# Logic_Engine_v0_1.net
KiCad netlist of a schematic drawn in EAGLE
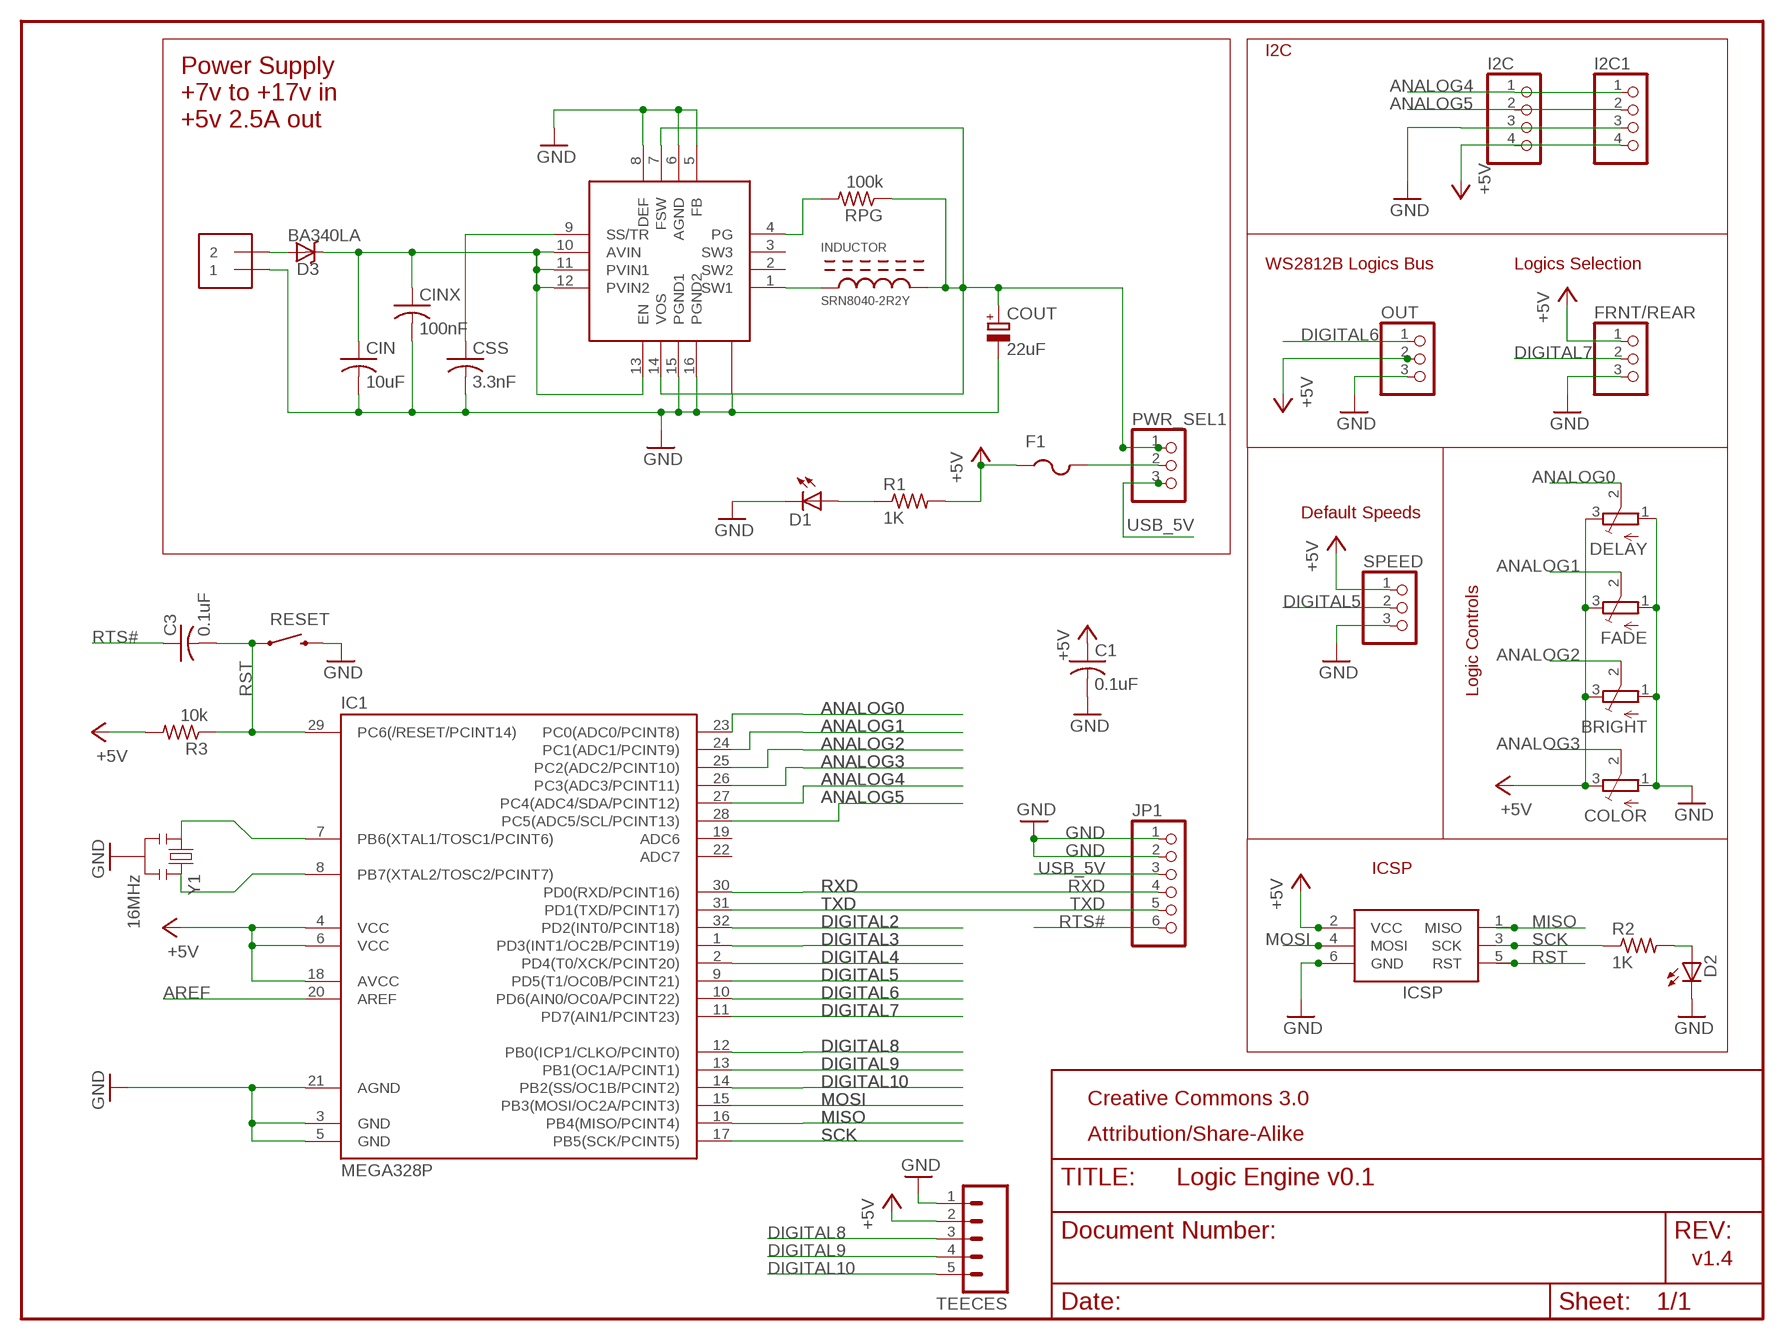
[diagram p0: schematic, sheet 1]

(export (version "E")
  (design (tool "Eeschema 10.0.6"))
  (components
    (comp (ref "BRIGHT")
      (value "TRIMPOT3364W")
      (footprint "eagle-import:3364")
      (libsource (lib "eagle-import") (part "TRIMPOT3364W"))
    )
    (comp (ref "C1")
      (value "0.1uF")
      (footprint "eagle-import:C0805K")
      (libsource (lib "eagle-import") (part "C-USC0805K"))
    )
    (comp (ref "C3")
      (value "0.1uF")
      (footprint "eagle-import:C0805K")
      (libsource (lib "eagle-import") (part "C-USC0805K"))
    )
    (comp (ref "CIN")
      (value "10uF")
      (footprint "eagle-import:C1206")
      (libsource (lib "eagle-import") (part "C-USC1206"))
    )
    (comp (ref "CINX")
      (value "100nF")
      (footprint "eagle-import:C0805K")
      (libsource (lib "eagle-import") (part "C-USC0805K"))
    )
    (comp (ref "COLOR")
      (value "TRIMPOT3364W")
      (footprint "eagle-import:3364")
      (libsource (lib "eagle-import") (part "TRIMPOT3364W"))
    )
    (comp (ref "COUT")
      (value "22uF")
      (footprint "eagle-import:CASE_B")
      (libsource (lib "eagle-import") (part "CAPACITOR_POL-CASE_B"))
    )
    (comp (ref "CSS")
      (value "3.3nF")
      (footprint "eagle-import:C0805K")
      (libsource (lib "eagle-import") (part "C-USC0805K"))
    )
    (comp (ref "D1")
      (value "LEDCHIPLED_1206")
      (footprint "eagle-import:CHIPLED_1206")
      (libsource (lib "eagle-import") (part "LEDCHIPLED_1206"))
    )
    (comp (ref "D2")
      (value "Green")
      (footprint "eagle-import:CHIPLED_1206")
      (libsource (lib "eagle-import") (part "LEDCHIPLED_1206"))
    )
    (comp (ref "D3")
      (value "BA340LA")
      (footprint "eagle-import:SMA-DIODE")
      (libsource (lib "eagle-import") (part "B340A"))
    )
    (comp (ref "DELAY")
      (value "TRIMPOT3364W")
      (footprint "eagle-import:3364")
      (libsource (lib "eagle-import") (part "TRIMPOT3364W"))
    )
    (comp (ref "EXT.PWR")
      (value "1X2-3.5MM")
      (footprint "eagle-import:1X2-3.5MM")
      (libsource (lib "eagle-import") (part "1X2-3.5MM"))
    )
    (comp (ref "F1")
      (value "PTCFUSE-1812")
      (footprint "eagle-import:1812")
      (libsource (lib "eagle-import") (part "PTCFUSE-1812"))
    )
    (comp (ref "FADE")
      (value "TRIMPOT3364W")
      (footprint "eagle-import:3364")
      (libsource (lib "eagle-import") (part "TRIMPOT3364W"))
    )
    (comp (ref "FRNT/REAR")
      (value "PINHD-1X3")
      (footprint "eagle-import:1X03")
      (libsource (lib "eagle-import") (part "PINHD-1X3"))
    )
    (comp (ref "I2C")
      (value "PINHD-1X4CB")
      (footprint "eagle-import:1X04-CB")
      (libsource (lib "eagle-import") (part "PINHD-1X4CB"))
    )
    (comp (ref "I2C1")
      (value "PINHD-1X4CB")
      (footprint "eagle-import:1X04-CB")
      (libsource (lib "eagle-import") (part "PINHD-1X4CB"))
    )
    (comp (ref "IC1")
      (value "MEGA328P")
      (footprint "eagle-import:TQFP32-08")
      (libsource (lib "eagle-import") (part "MEGA48/88/168-AU"))
    )
    (comp (ref "ICSP")
      (value "AVRISP-6")
      (footprint "eagle-import:AVRISP")
      (libsource (lib "eagle-import") (part "AVRISP-6"))
    )
    (comp (ref "INDUCTOR")
      (value "SRN8040-2R2Y")
      (footprint "eagle-import:SRN8040")
      (libsource (lib "eagle-import") (part "SRN8040"))
    )
    (comp (ref "JP1")
      (value "PINHD-1X6CLEAN")
      (footprint "eagle-import:1X06-CLEAN")
      (libsource (lib "eagle-import") (part "PINHD-1X6CLEAN"))
    )
    (comp (ref "OUT")
      (value "PINHD-1X3")
      (footprint "eagle-import:1X03")
      (libsource (lib "eagle-import") (part "PINHD-1X3"))
    )
    (comp (ref "PWR_SEL1")
      (value "PINHD-1X3")
      (footprint "eagle-import:1X03")
      (libsource (lib "eagle-import") (part "PINHD-1X3"))
    )
    (comp (ref "R1")
      (value "1K")
      (footprint "eagle-import:R0805")
      (libsource (lib "eagle-import") (part "R-US_R0805"))
    )
    (comp (ref "R2")
      (value "1K")
      (footprint "eagle-import:R0805")
      (libsource (lib "eagle-import") (part "R-US_R0805"))
    )
    (comp (ref "R3")
      (value "10k")
      (footprint "eagle-import:R0805")
      (libsource (lib "eagle-import") (part "R-US_R0805"))
    )
    (comp (ref "REG")
      (value "TPS62133")
      (footprint "eagle-import:TPS6213X")
      (libsource (lib "eagle-import") (part "TPS6213X"))
    )
    (comp (ref "RESET")
      (value "SWITCH-MOMENTARY-2SMD")
      (footprint "eagle-import:TACTILE_SWITCH_SMD")
      (libsource (lib "eagle-import") (part "SWITCH-MOMENTARY-2SMD"))
    )
    (comp (ref "RPG")
      (value "100k")
      (footprint "eagle-import:R0805")
      (libsource (lib "eagle-import") (part "R-US_R0805"))
    )
    (comp (ref "SPEED")
      (value "PINHD-1X3")
      (footprint "eagle-import:1X03")
      (libsource (lib "eagle-import") (part "PINHD-1X3"))
    )
    (comp (ref "TEECES")
      (value "M05PTH")
      (footprint "eagle-import:1X05")
      (libsource (lib "eagle-import") (part "M05PTH"))
    )
    (comp (ref "Y1")
      (value "16MHz")
      (footprint "eagle-import:RESONATOR-SMD")
      (libsource (lib "eagle-import") (part "RESONATOR16MHZ"))
    )
  )
  (nets
    (net (code "1") (name "+5V") (class "Default")
      (node (ref "BRIGHT") (pin "3") (pinfunction "E_3") (pintype "passive"))
      (node (ref "C1") (pin "1") (pinfunction "1_1") (pintype "passive"))
      (node (ref "COLOR") (pin "3") (pinfunction "E_3") (pintype "passive"))
      (node (ref "DELAY") (pin "3") (pinfunction "E_3") (pintype "passive"))
      (node (ref "F1") (pin "1") (pinfunction "1_1") (pintype "passive"))
      (node (ref "FADE") (pin "3") (pinfunction "E_3") (pintype "passive"))
      (node (ref "FRNT/REAR") (pin "1") (pinfunction "1_1") (pintype "passive"))
      (node (ref "I2C") (pin "4") (pinfunction "4_4") (pintype "passive"))
      (node (ref "I2C1") (pin "4") (pinfunction "4_4") (pintype "passive"))
      (node (ref "IC1") (pin "18") (pinfunction "AVCC_18") (pintype "passive"))
      (node (ref "IC1") (pin "4") (pinfunction "VCC_4") (pintype "power_in"))
      (node (ref "IC1") (pin "6") (pinfunction "VCC_6") (pintype "power_in"))
      (node (ref "ICSP") (pin "2") (pinfunction "VCC_2") (pintype "power_in"))
      (node (ref "OUT") (pin "2") (pinfunction "2_2") (pintype "passive"))
      (node (ref "R1") (pin "2") (pinfunction "2_2") (pintype "passive"))
      (node (ref "R3") (pin "2") (pinfunction "2_2") (pintype "passive"))
      (node (ref "SPEED") (pin "1") (pinfunction "1_1") (pintype "passive"))
      (node (ref "TEECES") (pin "2") (pinfunction "2_2") (pintype "passive"))
    )
    (net (code "2") (name "/ANALOG0") (class "Default")
      (node (ref "DELAY") (pin "2") (pinfunction "S_2") (pintype "passive"))
      (node (ref "IC1") (pin "23") (pinfunction "PC0(ADC0/PCINT8)_23") (pintype "bidirectional"))
    )
    (net (code "3") (name "/ANALOG1") (class "Default")
      (node (ref "FADE") (pin "2") (pinfunction "S_2") (pintype "passive"))
      (node (ref "IC1") (pin "24") (pinfunction "PC1(ADC1/PCINT9)_24") (pintype "bidirectional"))
    )
    (net (code "4") (name "/ANALOG2") (class "Default")
      (node (ref "BRIGHT") (pin "2") (pinfunction "S_2") (pintype "passive"))
      (node (ref "IC1") (pin "25") (pinfunction "PC2(ADC2/PCINT10)_25") (pintype "bidirectional"))
    )
    (net (code "5") (name "/ANALOG3") (class "Default")
      (node (ref "COLOR") (pin "2") (pinfunction "S_2") (pintype "passive"))
      (node (ref "IC1") (pin "26") (pinfunction "PC3(ADC3/PCINT11)_26") (pintype "bidirectional"))
    )
    (net (code "6") (name "/ANALOG4") (class "Default")
      (node (ref "I2C") (pin "1") (pinfunction "1_1") (pintype "passive"))
      (node (ref "I2C1") (pin "1") (pinfunction "1_1") (pintype "passive"))
      (node (ref "IC1") (pin "27") (pinfunction "PC4(ADC4/SDA/PCINT12)_27") (pintype "bidirectional"))
    )
    (net (code "7") (name "/ANALOG5") (class "Default")
      (node (ref "I2C") (pin "2") (pinfunction "2_2") (pintype "passive"))
      (node (ref "I2C1") (pin "2") (pinfunction "2_2") (pintype "passive"))
      (node (ref "IC1") (pin "28") (pinfunction "PC5(ADC5/SCL/PCINT13)_28") (pintype "bidirectional"))
    )
    (net (code "8") (name "/AREF") (class "Default")
      (node (ref "IC1") (pin "20") (pinfunction "AREF_20") (pintype "passive"))
    )
    (net (code "9") (name "/DIGITAL2") (class "Default")
      (node (ref "IC1") (pin "32") (pinfunction "PD2(INT0/PCINT18)_32") (pintype "bidirectional"))
    )
    (net (code "10") (name "/DIGITAL3") (class "Default")
      (node (ref "IC1") (pin "1") (pinfunction "PD3(INT1/OC2B/PCINT19)_1") (pintype "bidirectional"))
    )
    (net (code "11") (name "/DIGITAL4") (class "Default")
      (node (ref "IC1") (pin "2") (pinfunction "PD4(T0/XCK/PCINT20)_2") (pintype "bidirectional"))
    )
    (net (code "12") (name "/DIGITAL5") (class "Default")
      (node (ref "IC1") (pin "9") (pinfunction "PD5(T1/OC0B/PCINT21)_9") (pintype "bidirectional"))
      (node (ref "SPEED") (pin "2") (pinfunction "2_2") (pintype "passive"))
    )
    (net (code "13") (name "/DIGITAL6") (class "Default")
      (node (ref "IC1") (pin "10") (pinfunction "PD6(AIN0/OC0A/PCINT22)_10") (pintype "bidirectional"))
      (node (ref "OUT") (pin "1") (pinfunction "1_1") (pintype "passive"))
    )
    (net (code "14") (name "/DIGITAL7") (class "Default")
      (node (ref "FRNT/REAR") (pin "2") (pinfunction "2_2") (pintype "passive"))
      (node (ref "IC1") (pin "11") (pinfunction "PD7(AIN1/PCINT23)_11") (pintype "bidirectional"))
    )
    (net (code "15") (name "/DIGITAL8") (class "Default")
      (node (ref "IC1") (pin "12") (pinfunction "PB0(ICP1/CLKO/PCINT0)_12") (pintype "bidirectional"))
      (node (ref "TEECES") (pin "3") (pinfunction "3_3") (pintype "passive"))
    )
    (net (code "16") (name "/DIGITAL9") (class "Default")
      (node (ref "IC1") (pin "13") (pinfunction "PB1(OC1A/PCINT1)_13") (pintype "bidirectional"))
      (node (ref "TEECES") (pin "4") (pinfunction "4_4") (pintype "passive"))
    )
    (net (code "17") (name "/DIGITAL10") (class "Default")
      (node (ref "IC1") (pin "14") (pinfunction "PB2(SS/OC1B/PCINT2)_14") (pintype "bidirectional"))
      (node (ref "TEECES") (pin "5") (pinfunction "5_5") (pintype "passive"))
    )
    (net (code "18") (name "/MISO") (class "Default")
      (node (ref "IC1") (pin "16") (pinfunction "PB4(MISO/PCINT4)_16") (pintype "bidirectional"))
      (node (ref "ICSP") (pin "1") (pinfunction "MISO_1") (pintype "input"))
    )
    (net (code "19") (name "/MOSI") (class "Default")
      (node (ref "IC1") (pin "15") (pinfunction "PB3(MOSI/OC2A/PCINT3)_15") (pintype "bidirectional"))
      (node (ref "ICSP") (pin "4") (pinfunction "MOSI_4") (pintype "output"))
    )
    (net (code "20") (name "/RST") (class "Default")
      (node (ref "C3") (pin "2") (pinfunction "2_2") (pintype "passive"))
      (node (ref "IC1") (pin "29") (pinfunction "PC6(/RESET/PCINT14)_29") (pintype "bidirectional"))
      (node (ref "ICSP") (pin "5") (pinfunction "RST_5") (pintype "output"))
      (node (ref "R3") (pin "1") (pinfunction "1_1") (pintype "passive"))
      (node (ref "RESET") (pin "1") (pinfunction "1_1") (pintype "passive"))
    )
    (net (code "21") (name "/RTS#") (class "Default")
      (node (ref "C3") (pin "1") (pinfunction "1_1") (pintype "passive"))
      (node (ref "JP1") (pin "6") (pinfunction "6_6") (pintype "passive"))
    )
    (net (code "22") (name "/RXD") (class "Default")
      (node (ref "IC1") (pin "30") (pinfunction "PD0(RXD/PCINT16)_30") (pintype "bidirectional"))
      (node (ref "JP1") (pin "4") (pinfunction "4_4") (pintype "passive"))
    )
    (net (code "23") (name "/SCK") (class "Default")
      (node (ref "IC1") (pin "17") (pinfunction "PB5(SCK/PCINT5)_17") (pintype "bidirectional"))
      (node (ref "ICSP") (pin "3") (pinfunction "SCK_3") (pintype "output"))
      (node (ref "R2") (pin "1") (pinfunction "1_1") (pintype "passive"))
    )
    (net (code "24") (name "/TXD") (class "Default")
      (node (ref "IC1") (pin "31") (pinfunction "PD1(TXD/PCINT17)_31") (pintype "bidirectional"))
      (node (ref "JP1") (pin "5") (pinfunction "5_5") (pintype "passive"))
    )
    (net (code "25") (name "/USB_5V") (class "Default")
      (node (ref "JP1") (pin "3") (pinfunction "3_3") (pintype "passive"))
      (node (ref "PWR_SEL1") (pin "3") (pinfunction "3_3") (pintype "passive"))
    )
    (net (code "26") (name "GND") (class "Default")
      (node (ref "BRIGHT") (pin "1") (pinfunction "A_1") (pintype "passive"))
      (node (ref "C1") (pin "2") (pinfunction "2_2") (pintype "passive"))
      (node (ref "CIN") (pin "2") (pinfunction "2_2") (pintype "passive"))
      (node (ref "CINX") (pin "2") (pinfunction "2_2") (pintype "passive"))
      (node (ref "COLOR") (pin "1") (pinfunction "A_1") (pintype "passive"))
      (node (ref "COUT") (pin "-") (pinfunction "-_-") (pintype "passive"))
      (node (ref "CSS") (pin "2") (pinfunction "2_2") (pintype "passive"))
      (node (ref "D1") (pin "C") (pinfunction "C_C") (pintype "passive"))
      (node (ref "D2") (pin "C") (pinfunction "C_C") (pintype "passive"))
      (node (ref "DELAY") (pin "1") (pinfunction "A_1") (pintype "passive"))
      (node (ref "EXT.PWR") (pin "1") (pinfunction "1_1") (pintype "passive"))
      (node (ref "FADE") (pin "1") (pinfunction "A_1") (pintype "passive"))
      (node (ref "FRNT/REAR") (pin "3") (pinfunction "3_3") (pintype "passive"))
      (node (ref "I2C") (pin "3") (pinfunction "3_3") (pintype "passive"))
      (node (ref "I2C1") (pin "3") (pinfunction "3_3") (pintype "passive"))
      (node (ref "IC1") (pin "21") (pinfunction "AGND_21") (pintype "power_in"))
      (node (ref "IC1") (pin "3") (pinfunction "GND_3") (pintype "power_in"))
      (node (ref "IC1") (pin "5") (pinfunction "GND_5") (pintype "power_in"))
      (node (ref "ICSP") (pin "6") (pinfunction "GND_6") (pintype "power_in"))
      (node (ref "JP1") (pin "1") (pinfunction "1_1") (pintype "passive"))
      (node (ref "JP1") (pin "2") (pinfunction "2_2") (pintype "passive"))
      (node (ref "OUT") (pin "3") (pinfunction "3_3") (pintype "passive"))
      (node (ref "REG") (pin "15") (pinfunction "PGND1_15") (pintype "bidirectional"))
      (node (ref "REG") (pin "16") (pinfunction "PGND2_16") (pintype "bidirectional"))
      (node (ref "REG") (pin "17-THERMALPAD") (pinfunction "THERM_17-THERMALPAD") (pintype "bidirectional"))
      (node (ref "REG") (pin "5") (pinfunction "FB_5") (pintype "bidirectional"))
      (node (ref "REG") (pin "6") (pinfunction "AGND_6") (pintype "bidirectional"))
      (node (ref "REG") (pin "8") (pinfunction "DEF_8") (pintype "bidirectional"))
      (node (ref "RESET") (pin "3") (pinfunction "2_3") (pintype "passive"))
      (node (ref "SPEED") (pin "3") (pinfunction "3_3") (pintype "passive"))
      (node (ref "TEECES") (pin "1") (pinfunction "1_1") (pintype "passive"))
      (node (ref "Y1") (pin "2") (pinfunction "2_2") (pintype "passive"))
    )
    (net (code "27") (name "Net-(D1-PadA)") (class "Default")
      (node (ref "D1") (pin "A") (pinfunction "A_A") (pintype "passive"))
      (node (ref "R1") (pin "1") (pinfunction "1_1") (pintype "passive"))
    )
    (net (code "28") (name "Net-(D2-PadA)") (class "Default")
      (node (ref "D2") (pin "A") (pinfunction "A_A") (pintype "passive"))
      (node (ref "R2") (pin "2") (pinfunction "2_2") (pintype "passive"))
    )
    (net (code "29") (name "Net-(D3-PadA)") (class "Default")
      (node (ref "D3") (pin "A") (pinfunction "A_A") (pintype "passive"))
      (node (ref "EXT.PWR") (pin "2") (pinfunction "2_2") (pintype "passive"))
    )
    (net (code "30") (name "Net-(F1-Pad2)") (class "Default")
      (node (ref "F1") (pin "2") (pinfunction "2_2") (pintype "passive"))
      (node (ref "PWR_SEL1") (pin "2") (pinfunction "2_2") (pintype "passive"))
    )
    (net (code "31") (name "Net-(IC1-PB6(XTAL1{slash}TOSC1{slash}PCINT6))") (class "Default")
      (node (ref "IC1") (pin "7") (pinfunction "PB6(XTAL1/TOSC1/PCINT6)_7") (pintype "bidirectional"))
      (node (ref "Y1") (pin "1") (pinfunction "1_1") (pintype "passive"))
    )
    (net (code "32") (name "Net-(IC1-PB7(XTAL2{slash}TOSC2{slash}PCINT7))") (class "Default")
      (node (ref "IC1") (pin "8") (pinfunction "PB7(XTAL2/TOSC2/PCINT7)_8") (pintype "bidirectional"))
      (node (ref "Y1") (pin "3") (pinfunction "3_3") (pintype "passive"))
    )
    (net (code "33") (name "Net-(INDUCTOR-P1)") (class "Default")
      (node (ref "INDUCTOR") (pin "P$1") (pinfunction "P1_P$1") (pintype "bidirectional"))
      (node (ref "REG") (pin "1") (pinfunction "SW1_1") (pintype "bidirectional"))
    )
    (net (code "34") (name "Net-(INDUCTOR-P2)") (class "Default")
      (node (ref "COUT") (pin "+") (pinfunction "+_+") (pintype "passive"))
      (node (ref "INDUCTOR") (pin "P$2") (pinfunction "P2_P$2") (pintype "bidirectional"))
      (node (ref "PWR_SEL1") (pin "1") (pinfunction "1_1") (pintype "passive"))
      (node (ref "REG") (pin "14") (pinfunction "VOS_14") (pintype "bidirectional"))
      (node (ref "REG") (pin "7") (pinfunction "FSW_7") (pintype "bidirectional"))
      (node (ref "RPG") (pin "1") (pinfunction "1_1") (pintype "passive"))
    )
    (net (code "35") (name "Net-(REG-AVIN)") (class "Default")
      (node (ref "CIN") (pin "1") (pinfunction "1_1") (pintype "passive"))
      (node (ref "CINX") (pin "1") (pinfunction "1_1") (pintype "passive"))
      (node (ref "D3") (pin "C") (pinfunction "C_C") (pintype "passive"))
      (node (ref "REG") (pin "10") (pinfunction "AVIN_10") (pintype "bidirectional"))
      (node (ref "REG") (pin "11") (pinfunction "PVIN1_11") (pintype "bidirectional"))
      (node (ref "REG") (pin "12") (pinfunction "PVIN2_12") (pintype "bidirectional"))
      (node (ref "REG") (pin "13") (pinfunction "EN_13") (pintype "bidirectional"))
    )
    (net (code "36") (name "Net-(REG-PG)") (class "Default")
      (node (ref "REG") (pin "4") (pinfunction "PG_4") (pintype "bidirectional"))
      (node (ref "RPG") (pin "2") (pinfunction "2_2") (pintype "passive"))
    )
    (net (code "37") (name "Net-(REG-SS{slash}TR)") (class "Default")
      (node (ref "CSS") (pin "1") (pinfunction "1_1") (pintype "passive"))
      (node (ref "REG") (pin "9") (pinfunction "SS/TR_9") (pintype "bidirectional"))
    )
    (net (code "38") (name "unconnected-(IC1-ADC6-Pad19)") (class "Default")
      (node (ref "IC1") (pin "19") (pinfunction "ADC6_19") (pintype "passive"))
    )
    (net (code "39") (name "unconnected-(IC1-ADC7-Pad22)") (class "Default")
      (node (ref "IC1") (pin "22") (pinfunction "ADC7_22") (pintype "passive"))
    )
    (net (code "40") (name "unconnected-(REG-SW2-Pad2)") (class "Default")
      (node (ref "REG") (pin "2") (pinfunction "SW2_2") (pintype "bidirectional"))
    )
    (net (code "41") (name "unconnected-(REG-SW3-Pad3)") (class "Default")
      (node (ref "REG") (pin "3") (pinfunction "SW3_3") (pintype "bidirectional"))
    )
  )
)
